# DRV8244_Motor_Driver.net
KiCad netlist of a schematic drawn in Altium Designer
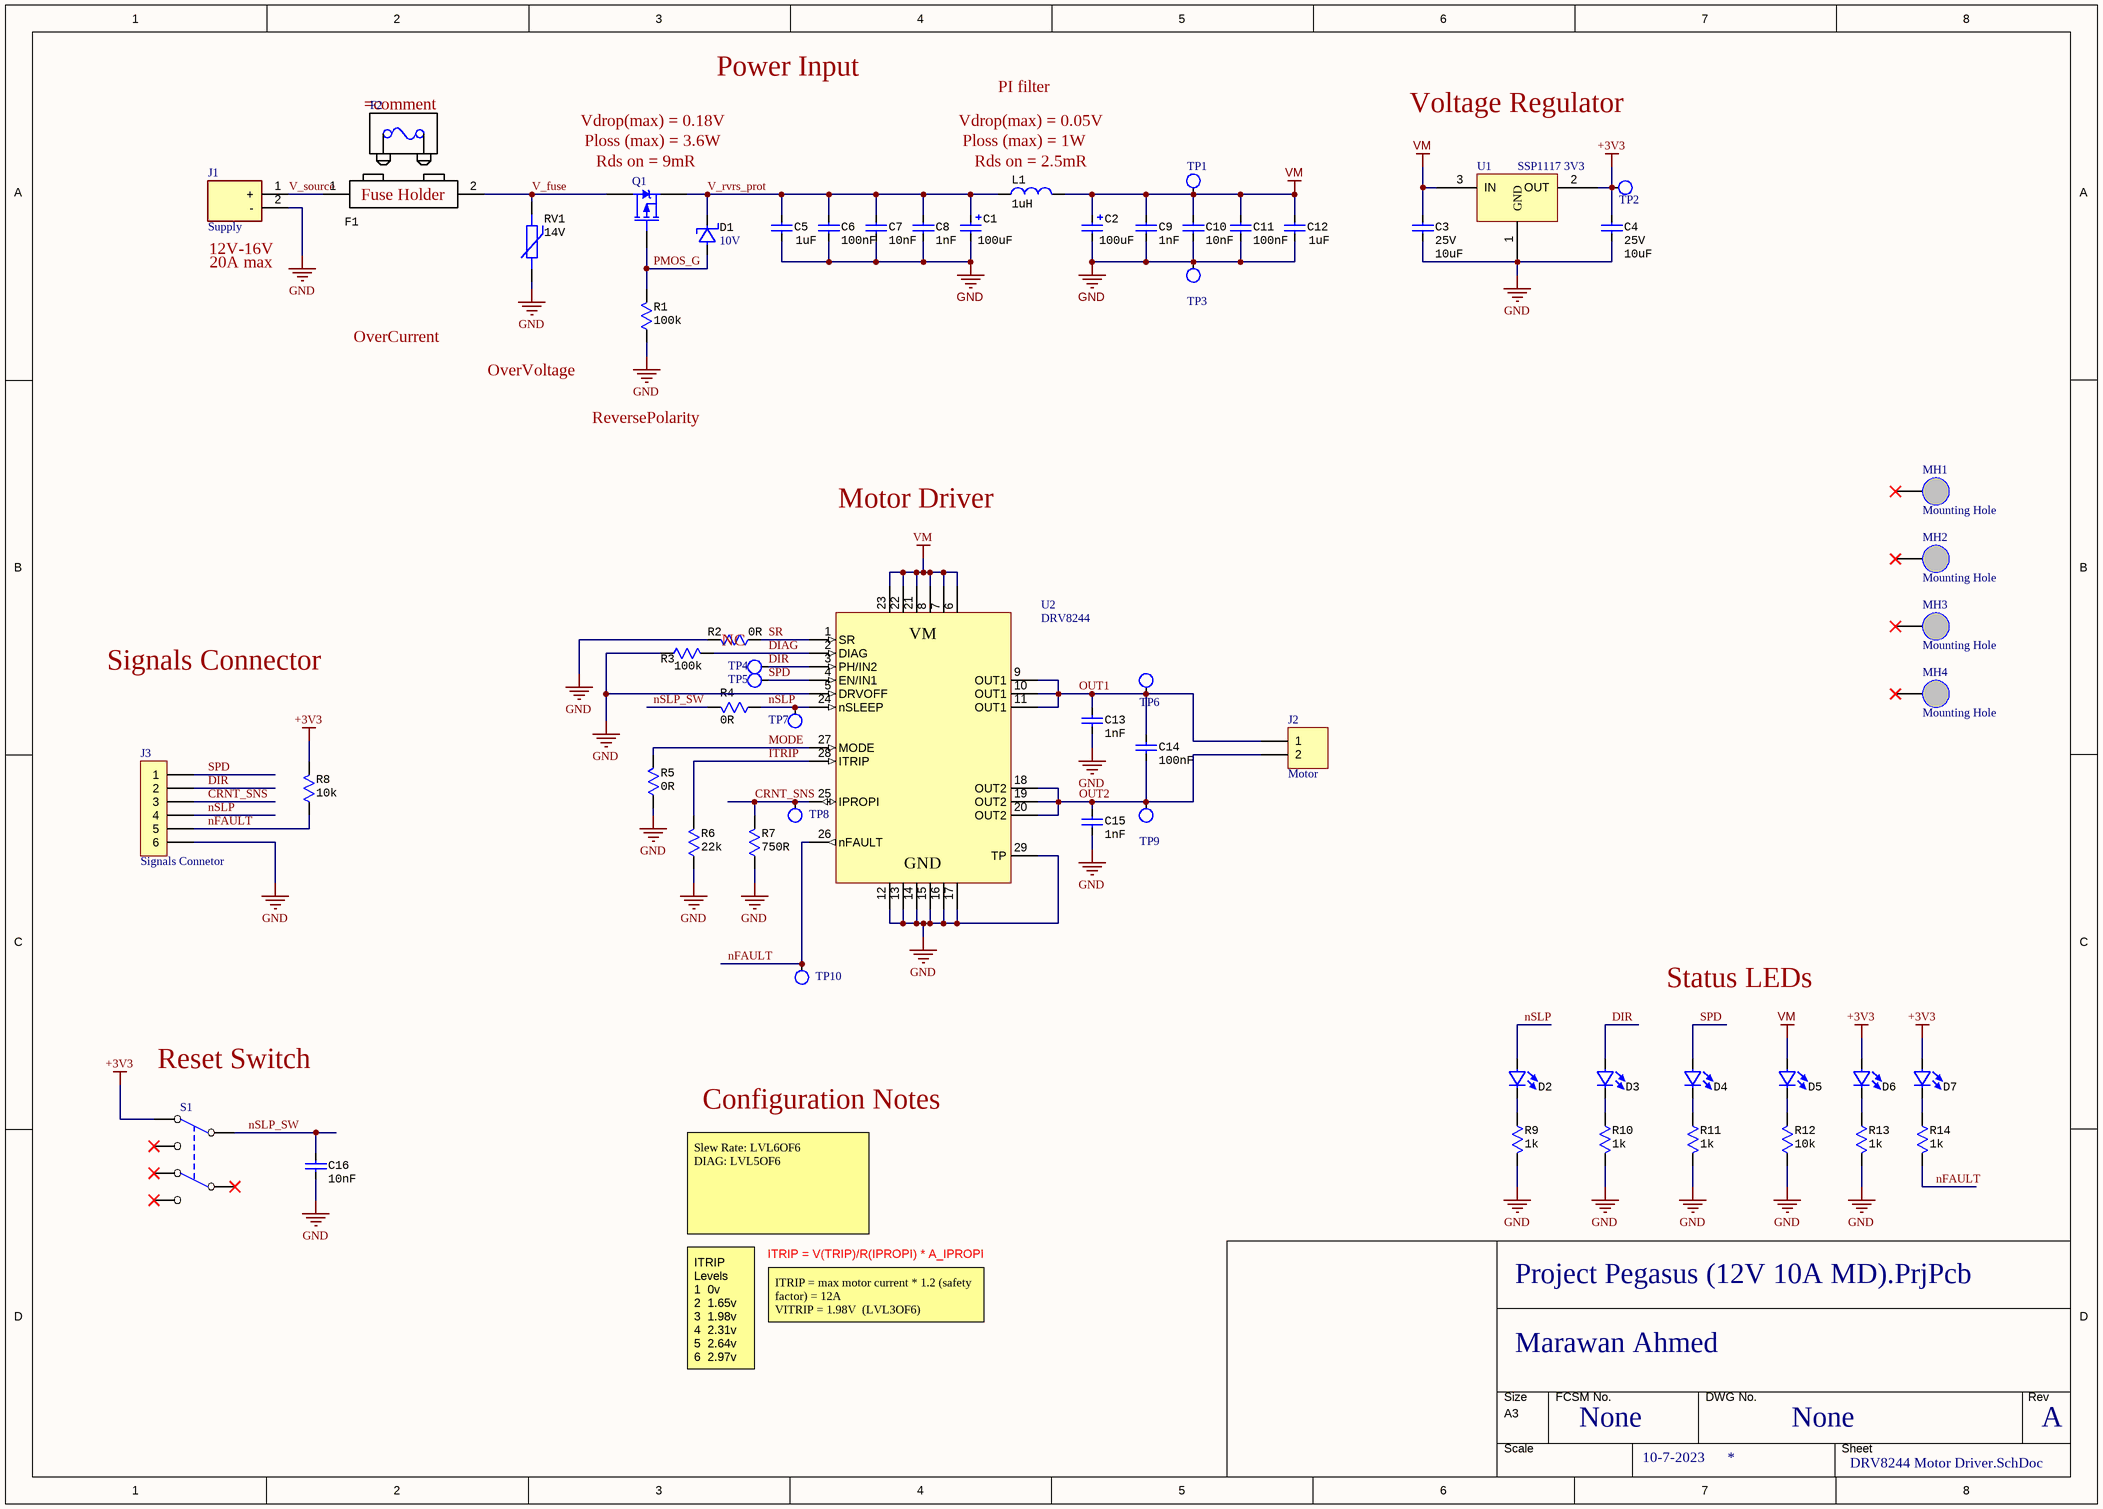
[diagram p0: DRV8244 Motor Driver.SchDoc]

(export (version "E")
  (design (tool "Eeschema 10.0.6"))
  (components
    (comp (ref "C1")
      (value "100uF")
      (footprint "CAP Electrolytic SMD G_10X10.3X10.2(CPOL-EU153CLV-1010)")
      (fields (field (name "MANUFACTURER") "ROQANG") (field (name "MANUFACTURER PART NUMBER") "RT1J101M1010"))
      (libsource (lib "Passive") (part "CAP ELEC 100uF 68V"))
    )
    (comp (ref "C2")
      (value "100uF")
      (footprint "CAP Electrolytic SMD G_10X10.3X10.2(CPOL-EU153CLV-1010)")
      (fields (field (name "MANUFACTURER") "ROQANG") (field (name "MANUFACTURER PART NUMBER") "RT1J101M1010"))
      (libsource (lib "Passive") (part "CAP ELEC 100uF 68V"))
    )
    (comp (ref "C3")
      (value "10uF")
      (footprint "CAP Ceramic SMD 1206")
      (description "Ceramic capacitor SMD-1206 10000nF (10uF) /25V X7R# K 10%, Samsung, RoHS/4k/")
      (fields
        (field (name "MANUFACTURER") "Samsung")
        (field (name "MANUFACTURER PART NUMBER") "CL31B106KAHNNNE")
        (field (name "VOLTAGE") "25V")
      )
      (libsource (lib "Passive") (part "CAP 1206 10uF 25V"))
    )
    (comp (ref "C4")
      (value "10uF")
      (footprint "CAP Ceramic SMD 1206")
      (description "Ceramic capacitor SMD-1206 10000nF (10uF) /25V X7R# K 10%, Samsung, RoHS/4k/")
      (fields
        (field (name "MANUFACTURER") "Samsung")
        (field (name "MANUFACTURER PART NUMBER") "CL31B106KAHNNNE")
        (field (name "VOLTAGE") "25V")
      )
      (libsource (lib "Passive") (part "CAP 1206 10uF 25V"))
    )
    (comp (ref "C5")
      (value "1uF")
      (footprint "CAP Ceramic SMD 0603")
      (description "0603 1 uF 50 V ±10% Tolerance X5R SMT Multilayer Ceramic Capacitor")
      (fields
        (field (name "MANUFACTURER") "Murata")
        (field (name "MANUFACTURER PART NUMBER") "GRM188R61H105KAALD")
      )
      (libsource (lib "Passive") (part "CAP 0603 1uF 50V"))
    )
    (comp (ref "C6")
      (value "100nF")
      (footprint "CAP Ceramic SMD 0603")
      (description "0603 0.1 uF 100 V ±10% Tolerance X7R Multilayer Ceramic Capacitor")
      (fields
        (field (name "MANUFACTURER") "Yageo")
        (field (name "MANUFACTURER PART NUMBER") "CC0603KRX7R0BB104")
      )
      (libsource (lib "Passive") (part "CAP 0603 100nF 100V"))
    )
    (comp (ref "C7")
      (value "10nF")
      (footprint "CAP Ceramic SMD 0603")
      (description "0603 10nF 50V ±10% Tolerance X7R Surface Mount Multilayer Ceramic Capacitor")
      (fields
        (field (name "MANUFACTURER") "Kyocera AVX")
        (field (name "MANUFACTURER PART NUMBER") "06035C103K4T2A")
        (field (name "CAPACITANCE") "10nF")
      )
      (libsource (lib "Passive") (part "CAP 0603 10nF 50V"))
    )
    (comp (ref "C8")
      (value "1nF")
      (footprint "CAP Ceramic SMD 0603")
      (description "CAP CER 1100PF 50V C0G/NP0 0603")
      (fields
        (field (name "MANUFACTURER") "YAGEO")
        (field (name "MANUFACTURER PART NUMBER") "CC0603KRX7R9BB102")
      )
      (libsource (lib "Passive") (part "CAP 0603 1nF 50V"))
    )
    (comp (ref "C9")
      (value "1nF")
      (footprint "CAP Ceramic SMD 0603")
      (description "CAP CER 1100PF 50V C0G/NP0 0603")
      (fields
        (field (name "MANUFACTURER") "YAGEO")
        (field (name "MANUFACTURER PART NUMBER") "CC0603KRX7R9BB102")
      )
      (libsource (lib "Passive") (part "CAP 0603 1nF 50V"))
    )
    (comp (ref "C10")
      (value "10nF")
      (footprint "CAP Ceramic SMD 0603")
      (description "0603 10nF 50V ±10% Tolerance X7R Surface Mount Multilayer Ceramic Capacitor")
      (fields
        (field (name "MANUFACTURER") "Kyocera AVX")
        (field (name "MANUFACTURER PART NUMBER") "06035C103K4T2A")
        (field (name "CAPACITANCE") "10nF")
      )
      (libsource (lib "Passive") (part "CAP 0603 10nF 50V"))
    )
    (comp (ref "C11")
      (value "100nF")
      (footprint "CAP Ceramic SMD 0603")
      (description "0603 0.1 uF 100 V ±10% Tolerance X7R Multilayer Ceramic Capacitor")
      (fields
        (field (name "MANUFACTURER") "Yageo")
        (field (name "MANUFACTURER PART NUMBER") "CC0603KRX7R0BB104")
      )
      (libsource (lib "Passive") (part "CAP 0603 100nF 100V"))
    )
    (comp (ref "C12")
      (value "1uF")
      (footprint "CAP Ceramic SMD 0603")
      (description "0603 1 uF 50 V ±10% Tolerance X5R SMT Multilayer Ceramic Capacitor")
      (fields
        (field (name "MANUFACTURER") "Murata")
        (field (name "MANUFACTURER PART NUMBER") "GRM188R61H105KAALD")
      )
      (libsource (lib "Passive") (part "CAP 0603 1uF 50V"))
    )
    (comp (ref "C13")
      (value "1nF")
      (footprint "CAP Ceramic SMD 0603")
      (description "CAP CER 1100PF 50V C0G/NP0 0603")
      (fields
        (field (name "MANUFACTURER") "YAGEO")
        (field (name "MANUFACTURER PART NUMBER") "CC0603KRX7R9BB102")
      )
      (libsource (lib "Passive") (part "CAP 0603 1nF 50V"))
    )
    (comp (ref "C14")
      (value "100nF")
      (footprint "CAP Ceramic SMD 0603")
      (description "0603 0.1 uF 100 V ±10% Tolerance X7R Multilayer Ceramic Capacitor")
      (fields
        (field (name "MANUFACTURER") "Yageo")
        (field (name "MANUFACTURER PART NUMBER") "CC0603KRX7R0BB104")
      )
      (libsource (lib "Passive") (part "CAP 0603 100nF 100V"))
    )
    (comp (ref "C15")
      (value "1nF")
      (footprint "CAP Ceramic SMD 0603")
      (description "CAP CER 1100PF 50V C0G/NP0 0603")
      (fields
        (field (name "MANUFACTURER") "YAGEO")
        (field (name "MANUFACTURER PART NUMBER") "CC0603KRX7R9BB102")
      )
      (libsource (lib "Passive") (part "CAP 0603 1nF 50V"))
    )
    (comp (ref "C16")
      (value "10nF")
      (footprint "CAP Ceramic SMD 0603")
      (description "0603 10nF 50V ±10% Tolerance X7R Surface Mount Multilayer Ceramic Capacitor")
      (fields
        (field (name "MANUFACTURER") "Kyocera AVX")
        (field (name "MANUFACTURER PART NUMBER") "06035C103K4T2A")
        (field (name "CAPACITANCE") "10nF")
      )
      (libsource (lib "Passive") (part "CAP 0603 10nF 50V"))
    )
    (comp (ref "D1")
      (value "10V")
      (footprint "Diode Single SMD SOD123")
      (description "±2.5% Single 470mW 10V SOD-123 Zener Diodes ROHS")
      (fields
        (field (name "MANUFACTURER") "Diodes Incorporated")
        (field (name "MANUFACTURER PART NUMBER") "DDZ10C-7")
      )
      (libsource (lib "diode") (part "DDZ10C-7"))
    )
    (comp (ref "D2")
      (value "~")
      (footprint "LED SMD 0805G")
      (description "emerald 0805 Light Emitting Diodes (LED) ROHS")
      (fields
        (field (name "MANUFACTURER") "FOSHAN Nationstar Optoelectronics")
        (field (name "MANUFACTURER PART NUMBER") "NCD0805G1")
      )
      (libsource (lib "diode") (part "LED 0805 Emerald"))
    )
    (comp (ref "D3")
      (value "~")
      (footprint "LED SMD 0805G")
      (description "emerald 0805 Light Emitting Diodes (LED) ROHS")
      (fields
        (field (name "MANUFACTURER") "FOSHAN Nationstar Optoelectronics")
        (field (name "MANUFACTURER PART NUMBER") "NCD0805G1")
      )
      (libsource (lib "diode") (part "LED 0805 Emerald"))
    )
    (comp (ref "D4")
      (value "~")
      (footprint "LED SMD 0805G")
      (description "emerald 0805 Light Emitting Diodes (LED) ROHS")
      (fields
        (field (name "MANUFACTURER") "FOSHAN Nationstar Optoelectronics")
        (field (name "MANUFACTURER PART NUMBER") "NCD0805G1")
      )
      (libsource (lib "diode") (part "LED 0805 Emerald"))
    )
    (comp (ref "D5")
      (value "~")
      (footprint "LED SMD 0805R")
      (description "red 0805 Light Emitting Diodes (LED) ROHS")
      (fields
        (field (name "MANUFACTURER") "FOSHAN Nationstar Optoelectronics")
        (field (name "MANUFACTURER PART NUMBER") "NCD0805R1")
      )
      (libsource (lib "diode") (part "LED 0805 Red"))
    )
    (comp (ref "D6")
      (value "~")
      (footprint "LED SMD 0805R")
      (description "red 0805 Light Emitting Diodes (LED) ROHS")
      (fields
        (field (name "MANUFACTURER") "FOSHAN Nationstar Optoelectronics")
        (field (name "MANUFACTURER PART NUMBER") "NCD0805R1")
      )
      (libsource (lib "diode") (part "LED 0805 Red"))
    )
    (comp (ref "D7")
      (value "~")
      (footprint "LED SMD 0805B")
      (description "blue 0805 Light Emitting Diodes (LED) ROHS")
      (fields
        (field (name "MANUFACTURER") "FOSHAN Nationstar Optoelectronics")
        (field (name "MANUFACTURER PART NUMBER") "NCD0805B2")
      )
      (libsource (lib "diode") (part "LED 0805 Blue"))
    )
    (comp (ref "F1")
      (value "XF-508P-A")
      (footprint "FUSE-TH_L19.8-W7.0_XF-508P-A")
      (description "Plugin Fuse Holders ROHS")
      (fields (field (name "MANUFACTURER") "XFCN"))
      (libsource (lib "Fuse") (part "Fuse Automotive holder"))
    )
    (comp (ref "F2")
      (value "25A")
      (description "32V Fuse Automotive Holder Blade 25A - Automotive Fuses ROHS")
      (fields
        (field (name "MANUFACTURER") "Littelfuse")
        (field (name "MANUFACTURER PART NUMBER") "0287025.PXCN")
      )
      (libsource (lib "Fuse") (part "Fuse Automotive 25A 0287025.PXCN"))
    )
    (comp (ref "J1")
      (value "Supply")
      (footprint "XT60PW-M")
      (description "Power Connectors ROHS")
      (fields
        (field (name "MANUFACTURER") "Changzhou Amass Elec")
        (field (name "MANUFACTURER PART NUMBER") "XT60PW-M")
      )
      (libsource (lib "Power connectors") (part "XT60PW-M"))
    )
    (comp (ref "J2")
      (value "Motor")
      (footprint "Connector screw terminal Block TH 1x2 9.5 WJ46-B")
      (fields (field (name "MANUFACTURER") "DIBO") (field (name "MANUFACTURER PART NUMBER") "DBT50G-9.5-2P"))
      (libsource (lib "Power connectors") (part "Barrier Block 1x2 9.5mm with cover"))
    )
    (comp (ref "J3")
      (value "Signals Connetor")
      (footprint "XH-6/2.5mm")
      (description "1x6P XH 1 2.5mm 6 Brass Plugin,P=2.5mm Wire To Board / Wire To Wire Connector ROHS")
      (fields
        (field (name "MANUFACTURER") "JST Sales America")
        (field (name "MANUFACTURER PART NUMBER") "B6B-XH-A(LF)(SN)")
      )
      (libsource (lib "Signal connectors") (part "JST XH2.5mm 1x6P"))
    )
    (comp (ref "L1")
      (value "1uH")
      (footprint "IND SMD SRP1265A")
      (description "29A 1uH ±20% 37A SMD Power Inductors ROHS")
      (fields
        (field (name "MANUFACTURER") "Chilisin Elec")
        (field (name "MANUFACTURER PART NUMBER") "MHCC12050-1R0M-R7")
        (field (name "INDUCTANCE") "1uH")
      )
      (libsource (lib "Passive") (part "MHCC12050-1R0M-R7"))
    )
    (comp (ref "MH1")
      (value "Mounting Hole")
      (footprint "Connector Mounting hole th 3.5mm")
      (libsource (lib "Bypass, Testpoint and Holes") (part "Mounting Hole"))
    )
    (comp (ref "MH2")
      (value "Mounting Hole")
      (footprint "Connector Mounting hole th 3.5mm")
      (libsource (lib "Bypass, Testpoint and Holes") (part "Mounting Hole"))
    )
    (comp (ref "MH3")
      (value "Mounting Hole")
      (footprint "Connector Mounting hole th 3.5mm")
      (libsource (lib "Bypass, Testpoint and Holes") (part "Mounting Hole"))
    )
    (comp (ref "MH4")
      (value "Mounting Hole")
      (footprint "Connector Mounting hole th 3.5mm")
      (libsource (lib "Bypass, Testpoint and Holes") (part "Mounting Hole"))
    )
    (comp (ref "Q1")
      (value "HYG110P04LQ2C2")
      (footprint "PQFN 5x6")
      (description "40V 55A 62.5W 9mΩ@10V,20A P Channel PDFN-8(5.9x5.2) MOSFETs ROHS")
      (fields (field (name "MANUFACTURER") "HUAYI"))
      (libsource (lib "Miscellaneous Transistor") (part "HYG110P04LQ2C2"))
    )
    (comp (ref "R1")
      (value "100k")
      (footprint "RES SMD 0603")
      (description "RES SMD 100K OHM 1% 1/10W 0603")
      (fields
        (field (name "MANUFACTURER") "Panasonic")
        (field (name "MANUFACTURER PART NUMBER") "ERJ3EKF1003V")
        (field (name "RESISTANCE") "100k")
      )
      (libsource (lib "Passive") (part "RES 0603 100k 1%"))
    )
    (comp (ref "R2")
      (value "0R")
      (footprint "RES SMD 0603")
      (description "ERJ Series 0603 0 Ohm 0.05 W Jumper Surface Mount Thick Film Chip Resistor")
      (fields (field (name "TOLERANCE") "1%") (field (name "MANUFACTURER") "Panasonic"))
      (libsource (lib "Passive") (part "RES 0603 0R 1%"))
    )
    (comp (ref "R3")
      (value "100k")
      (footprint "RES SMD 0603")
      (description "RES SMD 100K OHM 1% 1/10W 0603")
      (fields
        (field (name "MANUFACTURER") "Panasonic")
        (field (name "MANUFACTURER PART NUMBER") "ERJ3EKF1003V")
        (field (name "RESISTANCE") "100k")
      )
      (libsource (lib "Passive") (part "RES 0603 100k 1%"))
    )
    (comp (ref "R4")
      (value "0R")
      (footprint "RES SMD 0603")
      (description "ERJ Series 0603 0 Ohm 0.05 W Jumper Surface Mount Thick Film Chip Resistor")
      (fields (field (name "TOLERANCE") "1%") (field (name "MANUFACTURER") "Panasonic"))
      (libsource (lib "Passive") (part "RES 0603 0R 1%"))
    )
    (comp (ref "R5")
      (value "0R")
      (footprint "RES SMD 0603")
      (description "ERJ Series 0603 0 Ohm 0.05 W Jumper Surface Mount Thick Film Chip Resistor")
      (fields (field (name "TOLERANCE") "1%") (field (name "MANUFACTURER") "Panasonic"))
      (libsource (lib "Passive") (part "RES 0603 0R 1%"))
    )
    (comp (ref "R6")
      (value "22k")
      (footprint "RES SMD 0603")
      (description "100mW Thick Film Resistors ±5% ±200ppm/℃ 22kΩ 0603 Chip Resistor - Surface Mount ROHS")
      (fields
        (field (name "MANUFACTURER") "PANASONIC")
        (field (name "MANUFACTURER PART NUMBER") "ERJ3GEYJ223V")
        (field (name "RESISTANCE") "22k")
      )
      (libsource (lib "Passive") (part "RES 0603 22k 1%"))
    )
    (comp (ref "R7")
      (value "750R")
      (footprint "RES SMD 0603")
      (description "Res Thick Film 0603 750 Ohm 1% 1/10W ±100ppm/°C Molded SMD Punched Carrier T/R")
      (fields
        (field (name "MANUFACTURER") "Panasonic")
        (field (name "MANUFACTURER PART NUMBER") "ERJ-3EKF7500V")
      )
      (libsource (lib "Passive") (part "RES 0603 750R 1%"))
    )
    (comp (ref "R8")
      (value "10k")
      (footprint "RES SMD 0603")
      (description "Res Thick Film 0603 10K Ohm 1% 1/10W ±100ppm/°C Molded SMD Punched Carrier T/R")
      (fields
        (field (name "MANUFACTURER") "Panasonic")
        (field (name "MANUFACTURER PART NUMBER") "ERJ-3EKF1002V")
      )
      (libsource (lib "Passive") (part "RES 0603 10k 1%"))
    )
    (comp (ref "R9")
      (value "1k")
      (footprint "RES SMD 0603")
      (description "Res Thick Film 0603 1K Ohm 1% 1/10W ±100ppm/°C Molded SMD Punched Carrier T/R")
      (fields
        (field (name "MANUFACTURER") "Panasonic")
        (field (name "MANUFACTURER PART NUMBER") "ERJ3EKF1001V")
      )
      (libsource (lib "Passive") (part "RES 0603 1k 1%"))
    )
    (comp (ref "R10")
      (value "1k")
      (footprint "RES SMD 0603")
      (description "Res Thick Film 0603 1K Ohm 1% 1/10W ±100ppm/°C Molded SMD Punched Carrier T/R")
      (fields
        (field (name "MANUFACTURER") "Panasonic")
        (field (name "MANUFACTURER PART NUMBER") "ERJ3EKF1001V")
      )
      (libsource (lib "Passive") (part "RES 0603 1k 1%"))
    )
    (comp (ref "R11")
      (value "1k")
      (footprint "RES SMD 0603")
      (description "Res Thick Film 0603 1K Ohm 1% 1/10W ±100ppm/°C Molded SMD Punched Carrier T/R")
      (fields
        (field (name "MANUFACTURER") "Panasonic")
        (field (name "MANUFACTURER PART NUMBER") "ERJ3EKF1001V")
      )
      (libsource (lib "Passive") (part "RES 0603 1k 1%"))
    )
    (comp (ref "R12")
      (value "10k")
      (footprint "RES SMD 0603")
      (description "Res Thick Film 0603 10K Ohm 1% 1/10W ±100ppm/°C Molded SMD Punched Carrier T/R")
      (fields
        (field (name "MANUFACTURER") "Panasonic")
        (field (name "MANUFACTURER PART NUMBER") "ERJ-3EKF1002V")
      )
      (libsource (lib "Passive") (part "RES 0603 10k 1%"))
    )
    (comp (ref "R13")
      (value "1k")
      (footprint "RES SMD 0603")
      (description "Res Thick Film 0603 1K Ohm 1% 1/10W ±100ppm/°C Molded SMD Punched Carrier T/R")
      (fields
        (field (name "MANUFACTURER") "Panasonic")
        (field (name "MANUFACTURER PART NUMBER") "ERJ3EKF1001V")
      )
      (libsource (lib "Passive") (part "RES 0603 1k 1%"))
    )
    (comp (ref "R14")
      (value "1k")
      (footprint "RES SMD 0603")
      (description "Res Thick Film 0603 1K Ohm 1% 1/10W ±100ppm/°C Molded SMD Punched Carrier T/R")
      (fields
        (field (name "MANUFACTURER") "Panasonic")
        (field (name "MANUFACTURER PART NUMBER") "ERJ3EKF1001V")
      )
      (libsource (lib "Passive") (part "RES 0603 1k 1%"))
    )
    (comp (ref "RV1")
      (value "14V")
      (footprint "VAR 7.5mm")
      (description "Allowable voltage is 14VDC 11VAC\r\nVaristor Voltage 18V (15V~21.6V)\r\n Plugin Varistors ROHS")
      (fields
        (field (name "MANUFACTURER") "VDR Varistor")
        (field (name "MANUFACTURER PART NUMBER") "VDR-10D180L")
        (field (name "MAXVOLTAGE") "14V")
      )
      (libsource (lib "Varistor") (part "VAR TH 14V 18V"))
    )
    (comp (ref "S1")
      (value "PB-22E86C")
      (footprint "SWP-KFT DIP-8X8")
      (description "No lock Straight DPDT 30V 100000 Times 500mA Plugin Push Switches ROHS")
      (fields (field (name "MANUFACTURER PART NUMBER") "G-Switch"))
      (libsource (lib "Switches") (part "PB-22E86C"))
    )
    (comp (ref "TP1")
      (value "TestPoint")
      (footprint "TestPoint Surface 0.8mm")
      (libsource (lib "Bypass, Testpoint and Holes") (part "TestPoint"))
    )
    (comp (ref "TP2")
      (value "TestPoint")
      (footprint "TestPoint Surface 0.8mm")
      (libsource (lib "Bypass, Testpoint and Holes") (part "TestPoint"))
    )
    (comp (ref "TP3")
      (value "TestPoint")
      (footprint "TestPoint Surface 0.8mm")
      (libsource (lib "Bypass, Testpoint and Holes") (part "TestPoint"))
    )
    (comp (ref "TP4")
      (value "TestPoint")
      (footprint "TestPoint Surface 0.8mm")
      (libsource (lib "Bypass, Testpoint and Holes") (part "TestPoint"))
    )
    (comp (ref "TP5")
      (value "TestPoint")
      (footprint "TestPoint Surface 0.8mm")
      (libsource (lib "Bypass, Testpoint and Holes") (part "TestPoint"))
    )
    (comp (ref "TP6")
      (value "TestPoint")
      (footprint "TestPoint Surface 0.8mm")
      (libsource (lib "Bypass, Testpoint and Holes") (part "TestPoint"))
    )
    (comp (ref "TP7")
      (value "TestPoint")
      (footprint "TestPoint Surface 0.8mm")
      (libsource (lib "Bypass, Testpoint and Holes") (part "TestPoint"))
    )
    (comp (ref "TP8")
      (value "TestPoint")
      (footprint "TestPoint Surface 0.8mm")
      (libsource (lib "Bypass, Testpoint and Holes") (part "TestPoint"))
    )
    (comp (ref "TP9")
      (value "TestPoint")
      (footprint "TestPoint Surface 0.8mm")
      (libsource (lib "Bypass, Testpoint and Holes") (part "TestPoint"))
    )
    (comp (ref "TP10")
      (value "TestPoint")
      (footprint "TestPoint Surface 0.8mm")
      (libsource (lib "Bypass, Testpoint and Holes") (part "TestPoint"))
    )
    (comp (ref "U1")
      (value "SSP1117 3V3")
      (footprint "Linear reagulator SMD AMS1117")
      (description "Fixed Positive LDO Regulator, 3.3V, 1.3V Dropout, Load current 1A, Vin max = 20V")
      (fields
        (field (name "MANUFACTURER") "Shanghai Siproin Microelectronics")
        (field (name "MANUFACTURER PART NUMBER") "SSP1117-3.3V")
      )
      (libsource (lib "PMIC") (part "SSP1117 3V3"))
    )
    (comp (ref "U2")
      (value "DRV8244")
      (footprint "DRV8244")
      (fields
        (field (name "MANUFACTURER") "Texas Instruments")
        (field (name "MANUFACTURER PART NUMBER") "DRV8244SQDGQRQ1")
      )
      (libsource (lib "PMIC") (part "DRV8244"))
    )
  )
  (nets
    (net (code "1") (name "+3V3") (class "Default")
      (node (ref "C4") (pin "1") (pinfunction "1_1") (pintype "passive"))
      (node (ref "D6") (pin "1") (pinfunction "1_1") (pintype "passive"))
      (node (ref "D7") (pin "1") (pinfunction "1_1") (pintype "passive"))
      (node (ref "R8") (pin "2") (pinfunction "2_2") (pintype "passive"))
      (node (ref "S1") (pin "1") (pinfunction "1_1") (pintype "passive"))
      (node (ref "TP2") (pin "1") (pinfunction "1_1") (pintype "power_in"))
      (node (ref "U1") (pin "2") (pinfunction "OUT_2") (pintype "passive"))
    )
    (net (code "2") (name "/CRNT_SNS") (class "Default")
      (node (ref "J3") (pin "3") (pinfunction "3_3") (pintype "passive"))
      (node (ref "R7") (pin "2") (pinfunction "2_2") (pintype "passive"))
      (node (ref "TP8") (pin "1") (pinfunction "1_1") (pintype "power_in"))
      (node (ref "U2") (pin "25") (pinfunction "IPROPI_25") (pintype "bidirectional"))
    )
    (net (code "3") (name "/DIAG") (class "Default")
      (node (ref "R3") (pin "2") (pinfunction "2_2") (pintype "passive"))
      (node (ref "U2") (pin "2") (pinfunction "DIAG_2") (pintype "input"))
    )
    (net (code "4") (name "/DIR") (class "Default")
      (node (ref "D3") (pin "1") (pinfunction "1_1") (pintype "passive"))
      (node (ref "J3") (pin "2") (pinfunction "2_2") (pintype "passive"))
      (node (ref "TP4") (pin "1") (pinfunction "1_1") (pintype "power_in"))
      (node (ref "U2") (pin "3") (pinfunction "PH/IN2_3") (pintype "input"))
    )
    (net (code "5") (name "/ITRIP") (class "Default")
      (node (ref "R6") (pin "2") (pinfunction "2_2") (pintype "passive"))
      (node (ref "U2") (pin "28") (pinfunction "ITRIP_28") (pintype "input"))
    )
    (net (code "6") (name "/MODE") (class "Default")
      (node (ref "R5") (pin "2") (pinfunction "2_2") (pintype "passive"))
      (node (ref "U2") (pin "27") (pinfunction "MODE_27") (pintype "input"))
    )
    (net (code "7") (name "/OUT1") (class "Default")
      (node (ref "C13") (pin "1") (pinfunction "1_1") (pintype "passive"))
      (node (ref "C14") (pin "1") (pinfunction "1_1") (pintype "passive"))
      (node (ref "J2") (pin "1") (pinfunction "1_1") (pintype "passive"))
      (node (ref "TP6") (pin "1") (pinfunction "1_1") (pintype "power_in"))
      (node (ref "U2") (pin "10") (pinfunction "OUT1_10") (pintype "power_in"))
      (node (ref "U2") (pin "11") (pinfunction "OUT1_11") (pintype "power_in"))
      (node (ref "U2") (pin "9") (pinfunction "OUT1_9") (pintype "power_in"))
    )
    (net (code "8") (name "/OUT2") (class "Default")
      (node (ref "C14") (pin "2") (pinfunction "2_2") (pintype "passive"))
      (node (ref "C15") (pin "1") (pinfunction "1_1") (pintype "passive"))
      (node (ref "J2") (pin "2") (pinfunction "2_2") (pintype "passive"))
      (node (ref "TP9") (pin "1") (pinfunction "1_1") (pintype "power_in"))
      (node (ref "U2") (pin "18") (pinfunction "OUT2_18") (pintype "power_in"))
      (node (ref "U2") (pin "19") (pinfunction "OUT2_19") (pintype "power_in"))
      (node (ref "U2") (pin "20") (pinfunction "OUT2_20") (pintype "power_in"))
    )
    (net (code "9") (name "/PMOS_G") (class "Default")
      (node (ref "D1") (pin "1") (pinfunction "1_1") (pintype "passive"))
      (node (ref "Q1") (pin "1") (pinfunction "G_1") (pintype "passive"))
      (node (ref "R1") (pin "2") (pinfunction "2_2") (pintype "passive"))
    )
    (net (code "10") (name "/SPD") (class "Default")
      (node (ref "D4") (pin "1") (pinfunction "1_1") (pintype "passive"))
      (node (ref "J3") (pin "1") (pinfunction "1_1") (pintype "passive"))
      (node (ref "TP5") (pin "1") (pinfunction "1_1") (pintype "power_in"))
      (node (ref "U2") (pin "4") (pinfunction "EN/IN1_4") (pintype "input"))
    )
    (net (code "11") (name "/SR") (class "Default")
      (node (ref "R2") (pin "1") (pinfunction "1_1") (pintype "passive"))
      (node (ref "U2") (pin "1") (pinfunction "SR_1") (pintype "input"))
    )
    (net (code "12") (name "/V_fuse") (class "Default")
      (node (ref "F1") (pin "2") (pinfunction "2_2") (pintype "passive"))
      (node (ref "Q1") (pin "2") (pinfunction "D_2") (pintype "passive"))
      (node (ref "RV1") (pin "2") (pinfunction "2_2") (pintype "passive"))
    )
    (net (code "13") (name "/V_rvrs_prot") (class "Default")
      (node (ref "C1") (pin "1") (pinfunction "1_1") (pintype "passive"))
      (node (ref "C5") (pin "1") (pinfunction "1_1") (pintype "passive"))
      (node (ref "C6") (pin "1") (pinfunction "1_1") (pintype "passive"))
      (node (ref "C7") (pin "1") (pinfunction "1_1") (pintype "passive"))
      (node (ref "C8") (pin "1") (pinfunction "1_1") (pintype "passive"))
      (node (ref "D1") (pin "2") (pinfunction "2_2") (pintype "passive"))
      (node (ref "L1") (pin "2") (pinfunction "2_2") (pintype "passive"))
      (node (ref "Q1") (pin "3") (pinfunction "S_3") (pintype "passive"))
    )
    (net (code "14") (name "/V_source") (class "Default")
      (node (ref "F1") (pin "1") (pinfunction "1_1") (pintype "passive"))
      (node (ref "J1") (pin "1") (pinfunction "+_1") (pintype "passive"))
    )
    (net (code "15") (name "/nFAULT") (class "Default")
      (node (ref "J3") (pin "5") (pinfunction "5_5") (pintype "passive"))
      (node (ref "R14") (pin "2") (pinfunction "2_2") (pintype "passive"))
      (node (ref "R8") (pin "1") (pinfunction "1_1") (pintype "passive"))
      (node (ref "TP10") (pin "1") (pinfunction "1_1") (pintype "power_in"))
      (node (ref "U2") (pin "26") (pinfunction "nFAULT_26") (pintype "output"))
    )
    (net (code "16") (name "/nSLP") (class "Default")
      (node (ref "D2") (pin "1") (pinfunction "1_1") (pintype "passive"))
      (node (ref "J3") (pin "4") (pinfunction "4_4") (pintype "passive"))
      (node (ref "R4") (pin "1") (pinfunction "1_1") (pintype "passive"))
      (node (ref "TP7") (pin "1") (pinfunction "1_1") (pintype "power_in"))
      (node (ref "U2") (pin "24") (pinfunction "nSLEEP_24") (pintype "input"))
    )
    (net (code "17") (name "/nSLP_SW") (class "Default")
      (node (ref "C16") (pin "1") (pinfunction "1_1") (pintype "passive"))
      (node (ref "R4") (pin "2") (pinfunction "2_2") (pintype "passive"))
      (node (ref "S1") (pin "2") (pinfunction "2_2") (pintype "passive"))
    )
    (net (code "18") (name "GND") (class "Default")
      (node (ref "C1") (pin "2") (pinfunction "2_2") (pintype "passive"))
      (node (ref "C10") (pin "2") (pinfunction "2_2") (pintype "passive"))
      (node (ref "C11") (pin "2") (pinfunction "2_2") (pintype "passive"))
      (node (ref "C12") (pin "2") (pinfunction "2_2") (pintype "passive"))
      (node (ref "C13") (pin "2") (pinfunction "2_2") (pintype "passive"))
      (node (ref "C15") (pin "2") (pinfunction "2_2") (pintype "passive"))
      (node (ref "C16") (pin "2") (pinfunction "2_2") (pintype "passive"))
      (node (ref "C2") (pin "2") (pinfunction "2_2") (pintype "passive"))
      (node (ref "C3") (pin "2") (pinfunction "2_2") (pintype "passive"))
      (node (ref "C4") (pin "2") (pinfunction "2_2") (pintype "passive"))
      (node (ref "C5") (pin "2") (pinfunction "2_2") (pintype "passive"))
      (node (ref "C6") (pin "2") (pinfunction "2_2") (pintype "passive"))
      (node (ref "C7") (pin "2") (pinfunction "2_2") (pintype "passive"))
      (node (ref "C8") (pin "2") (pinfunction "2_2") (pintype "passive"))
      (node (ref "C9") (pin "2") (pinfunction "2_2") (pintype "passive"))
      (node (ref "J1") (pin "2") (pinfunction "-_2") (pintype "passive"))
      (node (ref "J3") (pin "6") (pinfunction "6_6") (pintype "passive"))
      (node (ref "R1") (pin "1") (pinfunction "1_1") (pintype "passive"))
      (node (ref "R10") (pin "2") (pinfunction "2_2") (pintype "passive"))
      (node (ref "R11") (pin "2") (pinfunction "2_2") (pintype "passive"))
      (node (ref "R12") (pin "1") (pinfunction "1_1") (pintype "passive"))
      (node (ref "R13") (pin "2") (pinfunction "2_2") (pintype "passive"))
      (node (ref "R2") (pin "2") (pinfunction "2_2") (pintype "passive"))
      (node (ref "R3") (pin "1") (pinfunction "1_1") (pintype "passive"))
      (node (ref "R5") (pin "1") (pinfunction "1_1") (pintype "passive"))
      (node (ref "R6") (pin "1") (pinfunction "1_1") (pintype "passive"))
      (node (ref "R7") (pin "1") (pinfunction "1_1") (pintype "passive"))
      (node (ref "R9") (pin "2") (pinfunction "2_2") (pintype "passive"))
      (node (ref "RV1") (pin "1") (pinfunction "1_1") (pintype "passive"))
      (node (ref "TP3") (pin "1") (pinfunction "1_1") (pintype "power_in"))
      (node (ref "U1") (pin "1") (pinfunction "GND_1") (pintype "passive"))
      (node (ref "U2") (pin "12") (pinfunction "GND_12") (pintype "power_in"))
      (node (ref "U2") (pin "13") (pinfunction "GND_13") (pintype "power_in"))
      (node (ref "U2") (pin "14") (pinfunction "GND_14") (pintype "power_in"))
      (node (ref "U2") (pin "15") (pinfunction "GND_15") (pintype "power_in"))
      (node (ref "U2") (pin "16") (pinfunction "GND_16") (pintype "power_in"))
      (node (ref "U2") (pin "17") (pinfunction "GND_17") (pintype "power_in"))
      (node (ref "U2") (pin "29") (pinfunction "TP_29") (pintype "power_in"))
      (node (ref "U2") (pin "5") (pinfunction "DRVOFF_5") (pintype "input"))
    )
    (net (code "19") (name "Net-(D2-Pad2)") (class "Default")
      (node (ref "D2") (pin "2") (pinfunction "2_2") (pintype "passive"))
      (node (ref "R9") (pin "1") (pinfunction "1_1") (pintype "passive"))
    )
    (net (code "20") (name "Net-(D3-Pad2)") (class "Default")
      (node (ref "D3") (pin "2") (pinfunction "2_2") (pintype "passive"))
      (node (ref "R10") (pin "1") (pinfunction "1_1") (pintype "passive"))
    )
    (net (code "21") (name "Net-(D4-Pad2)") (class "Default")
      (node (ref "D4") (pin "2") (pinfunction "2_2") (pintype "passive"))
      (node (ref "R11") (pin "1") (pinfunction "1_1") (pintype "passive"))
    )
    (net (code "22") (name "Net-(D5-Pad2)") (class "Default")
      (node (ref "D5") (pin "2") (pinfunction "2_2") (pintype "passive"))
      (node (ref "R12") (pin "2") (pinfunction "2_2") (pintype "passive"))
    )
    (net (code "23") (name "Net-(D6-Pad2)") (class "Default")
      (node (ref "D6") (pin "2") (pinfunction "2_2") (pintype "passive"))
      (node (ref "R13") (pin "1") (pinfunction "1_1") (pintype "passive"))
    )
    (net (code "24") (name "Net-(D7-Pad2)") (class "Default")
      (node (ref "D7") (pin "2") (pinfunction "2_2") (pintype "passive"))
      (node (ref "R14") (pin "1") (pinfunction "1_1") (pintype "passive"))
    )
    (net (code "25") (name "VM") (class "Default")
      (node (ref "C10") (pin "1") (pinfunction "1_1") (pintype "passive"))
      (node (ref "C11") (pin "1") (pinfunction "1_1") (pintype "passive"))
      (node (ref "C12") (pin "1") (pinfunction "1_1") (pintype "passive"))
      (node (ref "C2") (pin "1") (pinfunction "1_1") (pintype "passive"))
      (node (ref "C3") (pin "1") (pinfunction "1_1") (pintype "passive"))
      (node (ref "C9") (pin "1") (pinfunction "1_1") (pintype "passive"))
      (node (ref "D5") (pin "1") (pinfunction "1_1") (pintype "passive"))
      (node (ref "L1") (pin "1") (pinfunction "1_1") (pintype "passive"))
      (node (ref "TP1") (pin "1") (pinfunction "1_1") (pintype "power_in"))
      (node (ref "U1") (pin "3") (pinfunction "IN_3") (pintype "passive"))
      (node (ref "U2") (pin "21") (pinfunction "VM_21") (pintype "power_in"))
      (node (ref "U2") (pin "22") (pinfunction "VM_22") (pintype "power_in"))
      (node (ref "U2") (pin "23") (pinfunction "VM_23") (pintype "power_in"))
      (node (ref "U2") (pin "6") (pinfunction "VM_6") (pintype "power_in"))
      (node (ref "U2") (pin "7") (pinfunction "VM_7") (pintype "power_in"))
      (node (ref "U2") (pin "8") (pinfunction "VM_8") (pintype "power_in"))
    )
    (net (code "26") (name "unconnected-(MH1-Pad1)") (class "Default")
      (node (ref "MH1") (pin "1") (pinfunction "1_1") (pintype "passive+no_connect"))
    )
    (net (code "27") (name "unconnected-(MH2-Pad1)") (class "Default")
      (node (ref "MH2") (pin "1") (pinfunction "1_1") (pintype "passive+no_connect"))
    )
    (net (code "28") (name "unconnected-(MH3-Pad1)") (class "Default")
      (node (ref "MH3") (pin "1") (pinfunction "1_1") (pintype "passive+no_connect"))
    )
    (net (code "29") (name "unconnected-(MH4-Pad1)") (class "Default")
      (node (ref "MH4") (pin "1") (pinfunction "1_1") (pintype "passive+no_connect"))
    )
    (net (code "30") (name "unconnected-(S1-Pad3)") (class "Default")
      (node (ref "S1") (pin "3") (pinfunction "3_3") (pintype "passive+no_connect"))
    )
    (net (code "31") (name "unconnected-(S1-Pad4)") (class "Default")
      (node (ref "S1") (pin "4") (pinfunction "4_4") (pintype "passive+no_connect"))
    )
    (net (code "32") (name "unconnected-(S1-Pad5)") (class "Default")
      (node (ref "S1") (pin "5") (pinfunction "5_5") (pintype "passive+no_connect"))
    )
    (net (code "33") (name "unconnected-(S1-Pad6)") (class "Default")
      (node (ref "S1") (pin "6") (pinfunction "6_6") (pintype "passive+no_connect"))
    )
  )
)
